# GPS.net
KiCad netlist of a schematic drawn in Altium Designer
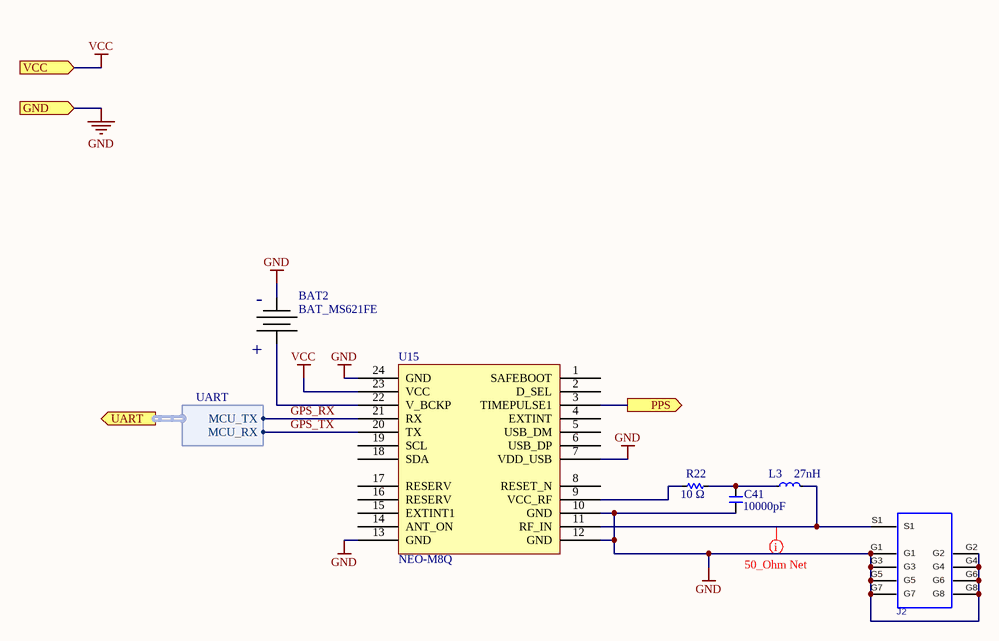
[diagram p0: GPS.SchDoc]

(export (version "E")
  (design (tool "Eeschema 10.0.6"))
  (components
    (comp (ref "BAT2")
      (value "BAT_MS621FE")
      (footprint "BATT_COINCELL_RECHARGEABLE")
      (description "MS621FE RECHARGEABLE COIN CELL BACKUP")
      (fields
        (field (name "MANUFACTURER") "Seiko Instruments")
        (field (name "MANUFACTURER PART NUMBER") "MS621FE-FL11E")
      )
      (libsource (lib "Stanford Student Space Initiative") (part "BAT_MS621FE"))
    )
    (comp (ref "C41")
      (value "490-1512-1-ND")
      (footprint "C0603")
      (description "CAP CER 0603 10000pF X7R 50V 10%")
      (fields
        (field (name "MANUFACTURER") "Murata Electronics North America")
        (field (name "CAPACITANCE (SHORTHAND)") "10000pF")
      )
      (libsource (lib "Stanford Student Space Initiative") (part "__template_cap"))
    )
    (comp (ref "J2")
      (value "SMA-J-P-X-ST-EM2")
      (footprint "SMA-J-P-X-ST-EM1")
      (libsource (lib "Stanford Student Space Initiative") (part "SMA-J-P-X-ST-EM1"))
    )
    (comp (ref "L3")
      (value "490-15373-1-ND")
      (footprint "R0402")
      (description "FIXED IND 27NH 680MA 288 MOHM")
      (fields
        (field (name "INDUCTANCE") "27nH")
        (field (name "MANUFACTURER") "Murata Electronics North America")
      )
      (libsource (lib "Stanford Student Space Initiative") (part "__template_inductor"))
    )
    (comp (ref "R22")
      (value "311-10.0HRCT-ND")
      (footprint "R0603")
      (description "RES SMD 10 OHM 1% 1/10W 0603")
      (fields
        (field (name "MANUFACTURER") "Yageo")
        (field (name "RESISTANCE") "10 Ω")
        (field (name "MANUFACTURER PART NUMBER") "RC0603FR-0710RL")
      )
      (libsource (lib "Stanford Student Space Initiative") (part "__template_resistor"))
    )
    (comp (ref "U15")
      (value "NEO-M8Q")
      (footprint "NEO_M8")
      (description "Receiver GNSS 24LCC")
      (libsource (lib "Stanford Student Space Initiative") (part "NEO_M8"))
    )
  )
  (nets
    (net (code "2") (name "/GPS_RX") (class "Default")
      (node (ref "U15") (pin "21") (pinfunction "RX_21") (pintype "passive"))
    )
    (net (code "3") (name "/GPS_TX") (class "Default")
      (node (ref "U15") (pin "20") (pinfunction "TX_20") (pintype "passive"))
    )
    (net (code "4") (name "/PPS") (class "Default")
      (node (ref "U15") (pin "3") (pinfunction "TIMEPULSE1_3") (pintype "passive"))
    )
    (net (code "6") (name "GND") (class "Default")
      (node (ref "BAT2") (pin "-") (pintype "passive"))
      (node (ref "C41") (pin "1") (pintype "passive"))
      (node (ref "J2") (pin "G1") (pinfunction "G1_G1") (pintype "passive"))
      (node (ref "J2") (pin "G2") (pinfunction "G2_G2") (pintype "passive"))
      (node (ref "J2") (pin "G3") (pinfunction "G3_G3") (pintype "passive"))
      (node (ref "J2") (pin "G4") (pinfunction "G4_G4") (pintype "passive"))
      (node (ref "J2") (pin "G5") (pinfunction "G5_G5") (pintype "passive"))
      (node (ref "J2") (pin "G6") (pinfunction "G6_G6") (pintype "passive"))
      (node (ref "J2") (pin "G7") (pinfunction "G7_G7") (pintype "passive"))
      (node (ref "J2") (pin "G8") (pinfunction "G8_G8") (pintype "passive"))
      (node (ref "U15") (pin "10") (pinfunction "GND_10") (pintype "passive"))
      (node (ref "U15") (pin "12") (pinfunction "GND_12") (pintype "passive"))
      (node (ref "U15") (pin "13") (pinfunction "GND_13") (pintype "passive"))
      (node (ref "U15") (pin "24") (pinfunction "GND_24") (pintype "passive"))
      (node (ref "U15") (pin "7") (pinfunction "VDD_USB_7") (pintype "passive"))
    )
    (net (code "7") (name "Net-(C41-Pad2)") (class "Default")
      (node (ref "C41") (pin "2") (pintype "passive"))
      (node (ref "L3") (pin "1") (pintype "passive"))
      (node (ref "R22") (pin "2") (pinfunction "2_2") (pintype "passive"))
    )
    (net (code "8") (name "Net-(U15-RF_IN)") (class "Default")
      (node (ref "J2") (pin "S1") (pinfunction "S1_S1") (pintype "passive"))
      (node (ref "L3") (pin "2") (pintype "passive"))
      (node (ref "U15") (pin "11") (pinfunction "RF_IN_11") (pintype "passive"))
    )
    (net (code "9") (name "Net-(U15-VCC_RF)") (class "Default")
      (node (ref "R22") (pin "1") (pinfunction "1_1") (pintype "passive"))
      (node (ref "U15") (pin "9") (pinfunction "VCC_RF_9") (pintype "passive"))
    )
    (net (code "10") (name "Net-(U15-V_BCKP)") (class "Default")
      (node (ref "BAT2") (pin "+") (pintype "passive"))
      (node (ref "U15") (pin "22") (pinfunction "V_BCKP_22") (pintype "passive"))
    )
    (net (code "11") (name "VCC") (class "Default")
      (node (ref "U15") (pin "23") (pinfunction "VCC_23") (pintype "passive"))
    )
    (net (code "12") (name "unconnected-(U15-ANT_ON-Pad14)") (class "Default")
      (node (ref "U15") (pin "14") (pinfunction "ANT_ON_14") (pintype "passive"))
    )
    (net (code "13") (name "unconnected-(U15-D_SEL-Pad2)") (class "Default")
      (node (ref "U15") (pin "2") (pinfunction "D_SEL_2") (pintype "passive"))
    )
    (net (code "14") (name "unconnected-(U15-EXTINT-Pad4)") (class "Default")
      (node (ref "U15") (pin "4") (pinfunction "EXTINT_4") (pintype "passive"))
    )
    (net (code "15") (name "unconnected-(U15-EXTINT1-Pad15)") (class "Default")
      (node (ref "U15") (pin "15") (pinfunction "EXTINT1_15") (pintype "passive"))
    )
    (net (code "16") (name "unconnected-(U15-RESERV-Pad16)") (class "Default")
      (node (ref "U15") (pin "16") (pinfunction "RESERV_16") (pintype "passive"))
    )
    (net (code "17") (name "unconnected-(U15-RESERV-Pad17)") (class "Default")
      (node (ref "U15") (pin "17") (pinfunction "RESERV_17") (pintype "passive"))
    )
    (net (code "18") (name "unconnected-(U15-RESET_N-Pad8)") (class "Default")
      (node (ref "U15") (pin "8") (pinfunction "RESET_N_8") (pintype "passive"))
    )
    (net (code "19") (name "unconnected-(U15-SAFEBOOT-Pad1)") (class "Default")
      (node (ref "U15") (pin "1") (pinfunction "SAFEBOOT_1") (pintype "passive"))
    )
    (net (code "20") (name "unconnected-(U15-SCL-Pad19)") (class "Default")
      (node (ref "U15") (pin "19") (pinfunction "SCL_19") (pintype "passive"))
    )
    (net (code "21") (name "unconnected-(U15-SDA-Pad18)") (class "Default")
      (node (ref "U15") (pin "18") (pinfunction "SDA_18") (pintype "passive"))
    )
    (net (code "22") (name "unconnected-(U15-USB_DM-Pad5)") (class "Default")
      (node (ref "U15") (pin "5") (pinfunction "USB_DM_5") (pintype "passive"))
    )
    (net (code "23") (name "unconnected-(U15-USB_DP-Pad6)") (class "Default")
      (node (ref "U15") (pin "6") (pinfunction "USB_DP_6") (pintype "passive"))
    )
  )
)
